# Main.net
KiCad netlist of a schematic drawn in Altium Designer
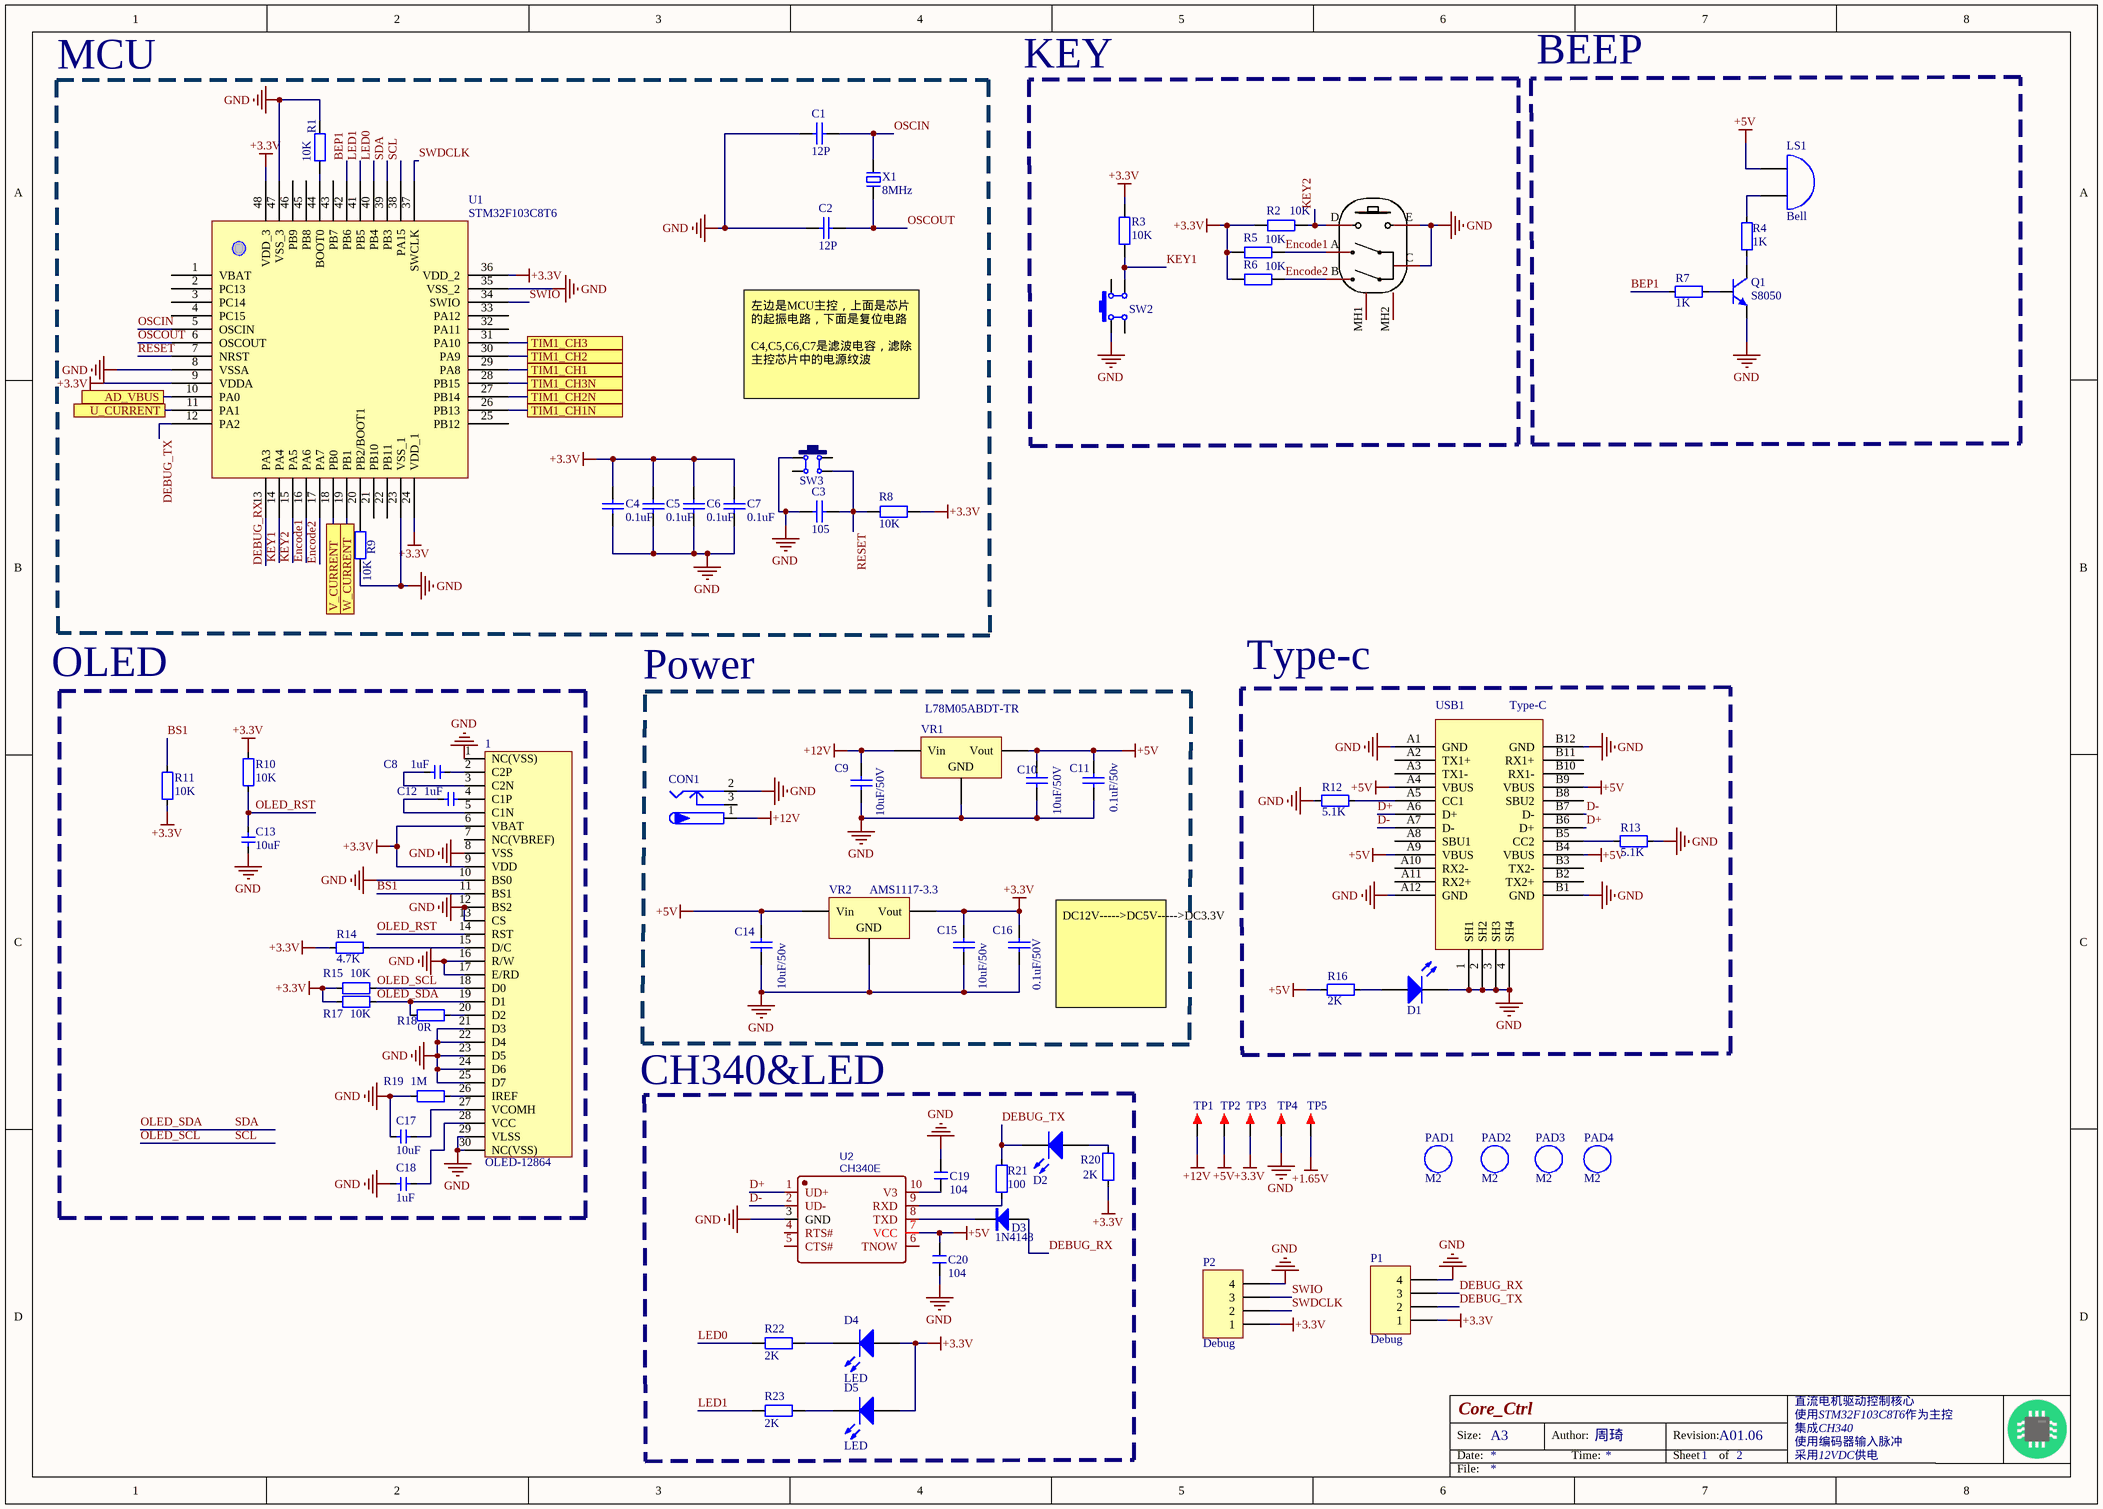
[diagram p0: Main.SchDoc]

(export (version "E")
  (design (tool "Eeschema 10.0.6"))
  (components
    (comp (ref "1")
      (value "OLED-12864")
      (footprint "OLED-12864-1.3-TOP")
      (description "显示屏")
      (libsource (lib "MyPcbLib") (part "OLED-12864"))
    )
    (comp (ref "C1")
      (value "12P")
      (footprint "C0603_L")
      (description "贴片电容")
      (libsource (lib "0.1 - 电阻-电容-电感-磁珠-电位器") (part "C"))
    )
    (comp (ref "C2")
      (value "12P")
      (footprint "C0603_L")
      (description "贴片电容")
      (libsource (lib "0.1 - 电阻-电容-电感-磁珠-电位器") (part "C"))
    )
    (comp (ref "C3")
      (value "105")
      (footprint "C0603_L")
      (description "贴片电容")
      (libsource (lib "0.1 - 电阻-电容-电感-磁珠-电位器") (part "C"))
    )
    (comp (ref "C4")
      (value "0.1uF")
      (footprint "C0603_L")
      (description "贴片电容")
      (libsource (lib "0.1 - 电阻-电容-电感-磁珠-电位器") (part "C"))
    )
    (comp (ref "C5")
      (value "0.1uF")
      (footprint "C0603_L")
      (description "贴片电容")
      (libsource (lib "0.1 - 电阻-电容-电感-磁珠-电位器") (part "C"))
    )
    (comp (ref "C6")
      (value "0.1uF")
      (footprint "C0603_L")
      (description "贴片电容")
      (libsource (lib "0.1 - 电阻-电容-电感-磁珠-电位器") (part "C"))
    )
    (comp (ref "C7")
      (value "0.1uF")
      (footprint "C0603_L")
      (description "贴片电容")
      (libsource (lib "0.1 - 电阻-电容-电感-磁珠-电位器") (part "C"))
    )
    (comp (ref "C8")
      (value "1uF")
      (footprint "C0603_L")
      (description "Capacitor")
      (libsource (lib "MyPcbLib") (part "电容-0402"))
    )
    (comp (ref "C9")
      (value "10uF/50V")
      (footprint "C1206_L")
      (description "C89632")
      (libsource (lib "Miscellaneous Devices") (part "Cap"))
    )
    (comp (ref "C10")
      (value "10uF/50V")
      (footprint "C1206_L")
      (description "C89632")
      (libsource (lib "Miscellaneous Devices") (part "Cap"))
    )
    (comp (ref "C11")
      (value "0.1uF/50v")
      (footprint "C1206_L")
      (libsource (lib "Miscellaneous Devices") (part "Cap"))
    )
    (comp (ref "C12")
      (value "1uF")
      (footprint "C0603_L")
      (description "Capacitor")
      (libsource (lib "MyPcbLib") (part "电容-0402"))
    )
    (comp (ref "C13")
      (value "10uF")
      (footprint "C0603_L")
      (description "Capacitor")
      (libsource (lib "MyPcbLib") (part "电容-0402"))
    )
    (comp (ref "C14")
      (value "10uF/50v")
      (footprint "C1206_L")
      (libsource (lib "Miscellaneous Devices") (part "Cap"))
    )
    (comp (ref "C15")
      (value "10uF/50v")
      (footprint "C1206_L")
      (libsource (lib "Miscellaneous Devices") (part "Cap"))
    )
    (comp (ref "C16")
      (value "0.1uF/50V")
      (footprint "C0603_L")
      (description "C89632")
      (libsource (lib "Miscellaneous Devices") (part "Cap"))
    )
    (comp (ref "C17")
      (value "10uF")
      (footprint "C0603_L")
      (description "Capacitor")
      (libsource (lib "MyPcbLib") (part "电容-0402"))
    )
    (comp (ref "C18")
      (value "1uF")
      (footprint "C0603_L")
      (description "Capacitor")
      (libsource (lib "MyPcbLib") (part "电容-0402"))
    )
    (comp (ref "C19")
      (value "104")
      (footprint "C0603_L")
      (description "无极性贴片电容")
      (fields (field (name "版权归属") "源创客"))
      (libsource (lib "9-电阻-电容-电感") (part "C"))
    )
    (comp (ref "C20")
      (value "104")
      (footprint "C0603_L")
      (description "无极性贴片电容")
      (fields (field (name "版权归属") "源创客"))
      (libsource (lib "9-电阻-电容-电感") (part "C"))
    )
    (comp (ref "CON1")
      (value "3.5*1.3")
      (footprint "DC-005")
      (description "低压电源接口")
      (libsource (lib "0.8 - 以太网-音频-Type-C USB插座") (part "P-DC"))
    )
    (comp (ref "D1")
      (value "LED0")
      (footprint "LED0603_R")
      (description "发光二极管")
      (fields (field (name "PUBLISHER") "Altium Limited"))
      (libsource (lib "18-常用器件") (part "LED0"))
    )
    (comp (ref "D2")
      (value "LED0")
      (footprint "LED0603_G")
      (description "发光二极管")
      (fields (field (name "PUBLISHER") "Altium Limited"))
      (libsource (lib "18-常用器件") (part "LED0"))
    )
    (comp (ref "D3")
      (value "1N4148")
      (footprint "SOD-123")
      (description "整流二极管")
      (fields (field (name "版权归属") "源创客"))
      (libsource (lib "10-二极管-整流桥") (part "M7"))
    )
    (comp (ref "D4")
      (value "LED")
      (footprint "LED0603_B")
      (description "发光二极管")
      (libsource (lib "0.3 - LED发光二极管") (part "LED"))
    )
    (comp (ref "D5")
      (value "LED")
      (footprint "LED0603_B")
      (description "发光二极管")
      (libsource (lib "0.3 - LED发光二极管") (part "LED"))
    )
    (comp (ref "LS1")
      (value "Bell")
      (footprint "BEEP 5x9x5.5")
      (description "Electrical Bell")
      (fields (field (name "PUBLISHER") "Altium Limited"))
      (libsource (lib "Miscellaneous Devices") (part "Bell"))
    )
    (comp (ref "P1")
      (value "Debug")
      (footprint "HDR2.54-LI-4P")
      (description "Header, 4-Pin")
      (fields (field (name "PUBLISHER") "Altium Limited"))
      (libsource (lib "Miscellaneous Connectors") (part "Header 4"))
    )
    (comp (ref "P2")
      (value "Debug")
      (footprint "HDR2.54-LI-4P")
      (description "Header, 4-Pin")
      (fields (field (name "PUBLISHER") "Altium Limited"))
      (libsource (lib "Miscellaneous Connectors") (part "Header 4"))
    )
    (comp (ref "PAD1")
      (value "M2")
      (footprint "M2")
      (description "铜柱孔")
      (libsource (lib "0.7 - 常用按键-开关-蜂鸣器-电池-测试点") (part "M3"))
    )
    (comp (ref "PAD2")
      (value "M2")
      (footprint "M2")
      (description "铜柱孔")
      (libsource (lib "0.7 - 常用按键-开关-蜂鸣器-电池-测试点") (part "M3"))
    )
    (comp (ref "PAD3")
      (value "M2")
      (footprint "M2")
      (description "铜柱孔")
      (libsource (lib "0.7 - 常用按键-开关-蜂鸣器-电池-测试点") (part "M3"))
    )
    (comp (ref "PAD4")
      (value "M2")
      (footprint "M2")
      (description "铜柱孔")
      (libsource (lib "0.7 - 常用按键-开关-蜂鸣器-电池-测试点") (part "M3"))
    )
    (comp (ref "Q1")
      (value "S8050")
      (footprint "SOT23-3N")
      (description "高频放大-NPN型")
      (libsource (lib "0.4 - 三极管-场效应管-可控硅") (part "8050-SMD"))
    )
    (comp (ref "R1")
      (value "10K")
      (footprint "R0603_L")
      (description "贴片电阻")
      (libsource (lib "0.1 - 电阻-电容-电感-磁珠-电位器") (part "R"))
    )
    (comp (ref "R2")
      (value "10K")
      (footprint "R0603_L")
      (description "贴片电阻")
      (libsource (lib "0.1 - 电阻-电容-电感-磁珠-电位器") (part "R"))
    )
    (comp (ref "R3")
      (value "10K")
      (footprint "R0603_L")
      (description "贴片电阻")
      (libsource (lib "0.1 - 电阻-电容-电感-磁珠-电位器") (part "R"))
    )
    (comp (ref "R4")
      (value "1K")
      (footprint "R0603_L")
      (description "Resistor")
      (libsource (lib "MyPcbLib") (part "电阻-0402"))
    )
    (comp (ref "R5")
      (value "10K")
      (footprint "R0603_L")
      (description "贴片电阻")
      (libsource (lib "0.1 - 电阻-电容-电感-磁珠-电位器") (part "R"))
    )
    (comp (ref "R6")
      (value "10K")
      (footprint "R0603_L")
      (description "贴片电阻")
      (libsource (lib "0.1 - 电阻-电容-电感-磁珠-电位器") (part "R"))
    )
    (comp (ref "R7")
      (value "1K")
      (footprint "R0603_L")
      (description "Resistor")
      (libsource (lib "") (part "电阻-0402_1"))
    )
    (comp (ref "R8")
      (value "10K")
      (footprint "R0603_L")
      (description "贴片电阻")
      (libsource (lib "0.1 - 电阻-电容-电感-磁珠-电位器") (part "R"))
    )
    (comp (ref "R9")
      (value "10K")
      (footprint "R0603_L")
      (description "贴片电阻")
      (libsource (lib "0.1 - 电阻-电容-电感-磁珠-电位器") (part "R"))
    )
    (comp (ref "R10")
      (value "10K")
      (footprint "R0603_L")
      (description "Resistor")
      (libsource (lib "MyPcbLib") (part "电阻-0402"))
    )
    (comp (ref "R11")
      (value "10K")
      (footprint "R0603_L")
      (description "Resistor")
      (libsource (lib "MyPcbLib") (part "电阻-0402"))
    )
    (comp (ref "R12")
      (value "5.1K")
      (footprint "R0603_L")
      (description "Resistor")
      (libsource (lib "") (part "电阻-0402_1"))
    )
    (comp (ref "R13")
      (value "5.1K")
      (footprint "R0603_L")
      (description "Resistor")
      (libsource (lib "") (part "电阻-0402_2"))
    )
    (comp (ref "R14")
      (value "4.7K")
      (footprint "R0603_L")
      (description "Resistor")
      (libsource (lib "") (part "电阻-0402_2"))
    )
    (comp (ref "R15")
      (value "10K")
      (footprint "R0603_L")
      (description "Resistor")
      (libsource (lib "") (part "电阻-0402_1"))
    )
    (comp (ref "R16")
      (value "2K")
      (footprint "R0603_L")
      (description "Resistor")
      (libsource (lib "") (part "电阻-0402_1"))
    )
    (comp (ref "R17")
      (value "10K")
      (footprint "R0603_L")
      (description "Resistor")
      (libsource (lib "") (part "电阻-0402_1"))
    )
    (comp (ref "R18")
      (value "0R")
      (footprint "R0603_L")
      (description "Resistor")
      (libsource (lib "") (part "电阻-0402_2"))
    )
    (comp (ref "R19")
      (value "1M")
      (footprint "R0603_L")
      (description "Resistor")
      (libsource (lib "") (part "电阻-0402_1"))
    )
    (comp (ref "R20")
      (value "2K")
      (footprint "R0603_L")
      (description "Resistor")
      (libsource (lib "MyPcbLib") (part "电阻-0402"))
    )
    (comp (ref "R21")
      (value "100")
      (footprint "R0603_L")
      (description "Resistor")
      (libsource (lib "") (part "电阻-0402_3"))
    )
    (comp (ref "R22")
      (value "2K")
      (footprint "R0603_L")
      (description "贴片电阻")
      (libsource (lib "0.1 - 电阻-电容-电感-磁珠-电位器") (part "R"))
    )
    (comp (ref "R23")
      (value "2K")
      (footprint "R0603_L")
      (description "贴片电阻")
      (libsource (lib "0.1 - 电阻-电容-电感-磁珠-电位器") (part "R"))
    )
    (comp (ref "SW1")
      (value "EC11K1524406")
      (footprint "SW-TH_EC11K1524406")
      (fields (field (name "MANUFACTURER") "ALPSALPINE(阿尔卑斯阿尔派)"))
      (libsource (lib "altium-import") (part "root_0_EC11K1524406_"))
    )
    (comp (ref "SW2")
      (value "12x12x5")
      (footprint "SW DIP-12*12*4.3")
      (description "直插12x12轻触开关")
      (libsource (lib "0.7 - 常用按键-开关-蜂鸣器-电池-测试点") (part "TSW DIP-12x12"))
    )
    (comp (ref "SW3")
      (value "6x6x5")
      (footprint "SW SMD-6*6*5")
      (description "贴片6x6轻触开关")
      (fields (field (name "版权归属") "源创客"))
      (libsource (lib "5-按键-开关") (part "TSW SMD-6x6"))
    )
    (comp (ref "TP1")
      (value "TEST")
      (footprint "TEST 1.6")
      (description "测试点")
      (libsource (lib "0.7 - 常用按键-开关-蜂鸣器-电池-测试点") (part "TEST"))
    )
    (comp (ref "TP2")
      (value "TEST")
      (footprint "TEST 1.6")
      (description "测试点")
      (libsource (lib "0.7 - 常用按键-开关-蜂鸣器-电池-测试点") (part "TEST"))
    )
    (comp (ref "TP3")
      (value "TEST")
      (footprint "TEST 1.6")
      (description "测试点")
      (libsource (lib "0.7 - 常用按键-开关-蜂鸣器-电池-测试点") (part "TEST"))
    )
    (comp (ref "TP4")
      (value "TEST")
      (footprint "TEST 1.6")
      (description "测试点")
      (libsource (lib "0.7 - 常用按键-开关-蜂鸣器-电池-测试点") (part "TEST"))
    )
    (comp (ref "TP5")
      (value "TEST")
      (footprint "TEST 1.6")
      (description "测试点")
      (libsource (lib "0.7 - 常用按键-开关-蜂鸣器-电池-测试点") (part "TEST"))
    )
    (comp (ref "U1")
      (value "STM32F103C8T6")
      (footprint "LQFP48-7*7")
      (libsource (lib "STM32F103C8T6") (part "STM32F103C8T6"))
    )
    (comp (ref "U2")
      (value "CH340E")
      (footprint "MSOP10_M")
      (fields (field (name "BOM_SUPPLIER PART") "C99652") (field (name "SUBPART_NO") "1"))
      (libsource (lib "altium-import") (part "root_0_CH340E_"))
    )
    (comp (ref "USB1")
      (value "Type-C")
      (footprint "USB-C-SMD_16P")
      (libsource (lib "MyPcbLib") (part "USB-Type-C-TOP"))
    )
    (comp (ref "VR1")
      (value "L78M05ABDT-TR")
      (footprint "TO-252")
      (description "低压差线性稳压(LDO)")
      (libsource (lib "LDO") (part "TO-252-2 L78M05ABDT-TR"))
    )
    (comp (ref "VR2")
      (value "AMS1117-3.3")
      (footprint "SOT223_L")
      (description "低压差线性稳压(LDO)")
      (libsource (lib "Miscellaneous Devices LC") (part "SOT-223 AMS1117-3.3"))
    )
    (comp (ref "X1")
      (value "8MHz")
      (footprint "OSC HC-49SMD")
      (description "2脚无源脚晶振")
      (libsource (lib "0.5 - 保险丝-晶振-光耦") (part "XTAL-2P"))
    )
  )
  (nets
    (net (code "1") (name "+1.65V") (class "Default")
      (node (ref "TP5") (pin "1") (pinfunction "1_1") (pintype "passive"))
    )
    (net (code "2") (name "+3.3V") (class "Default")
      (node (ref "1") (pin "6") (pinfunction "VBAT_6") (pintype "passive"))
      (node (ref "1") (pin "9") (pinfunction "VDD_9") (pintype "passive"))
      (node (ref "C15") (pin "2") (pinfunction "2_2") (pintype "passive"))
      (node (ref "C16") (pin "2") (pinfunction "2_2") (pintype "passive"))
      (node (ref "C4") (pin "1") (pinfunction "1_1") (pintype "passive"))
      (node (ref "C5") (pin "1") (pinfunction "1_1") (pintype "passive"))
      (node (ref "C6") (pin "1") (pinfunction "1_1") (pintype "passive"))
      (node (ref "C7") (pin "1") (pinfunction "1_1") (pintype "passive"))
      (node (ref "D4") (pin "1") (pinfunction "A_1") (pintype "passive"))
      (node (ref "D5") (pin "1") (pinfunction "A_1") (pintype "passive"))
      (node (ref "P1") (pin "1") (pinfunction "1_1") (pintype "passive"))
      (node (ref "P2") (pin "1") (pinfunction "1_1") (pintype "passive"))
      (node (ref "R10") (pin "2") (pinfunction "2_2") (pintype "passive"))
      (node (ref "R11") (pin "1") (pinfunction "1_1") (pintype "passive"))
      (node (ref "R14") (pin "2") (pinfunction "2_2") (pintype "passive"))
      (node (ref "R15") (pin "1") (pinfunction "1_1") (pintype "passive"))
      (node (ref "R17") (pin "1") (pinfunction "1_1") (pintype "passive"))
      (node (ref "R2") (pin "2") (pinfunction "2_2") (pintype "passive"))
      (node (ref "R20") (pin "1") (pinfunction "1_1") (pintype "passive"))
      (node (ref "R3") (pin "2") (pinfunction "2_2") (pintype "passive"))
      (node (ref "R5") (pin "2") (pinfunction "2_2") (pintype "passive"))
      (node (ref "R6") (pin "2") (pinfunction "2_2") (pintype "passive"))
      (node (ref "R8") (pin "2") (pinfunction "2_2") (pintype "passive"))
      (node (ref "TP3") (pin "1") (pinfunction "1_1") (pintype "passive"))
      (node (ref "U1") (pin "24") (pinfunction "VDD_1_24") (pintype "passive"))
      (node (ref "U1") (pin "36") (pinfunction "VDD_2_36") (pintype "passive"))
      (node (ref "U1") (pin "48") (pinfunction "VDD_3_48") (pintype "passive"))
      (node (ref "U1") (pin "9") (pinfunction "VDDA_9") (pintype "passive"))
      (node (ref "VR2") (pin "2") (pinfunction "Vout_2") (pintype "passive"))
    )
    (net (code "3") (name "+5V") (class "Default")
      (node (ref "C10") (pin "2") (pinfunction "2_2") (pintype "passive"))
      (node (ref "C11") (pin "2") (pinfunction "2_2") (pintype "passive"))
      (node (ref "C14") (pin "2") (pinfunction "2_2") (pintype "passive"))
      (node (ref "C20") (pin "1") (pinfunction "1_1") (pintype "passive"))
      (node (ref "LS1") (pin "1") (pinfunction "A_1") (pintype "passive"))
      (node (ref "R16") (pin "1") (pinfunction "1_1") (pintype "passive"))
      (node (ref "TP2") (pin "1") (pinfunction "1_1") (pintype "passive"))
      (node (ref "U2") (pin "7") (pinfunction "VCC_7") (pintype "passive"))
      (node (ref "USB1") (pin "A4") (pinfunction "VBUS_A4") (pintype "passive"))
      (node (ref "USB1") (pin "A9") (pinfunction "VBUS_A9") (pintype "passive"))
      (node (ref "USB1") (pin "B4") (pinfunction "VBUS_B4") (pintype "passive"))
      (node (ref "USB1") (pin "B9") (pinfunction "VBUS_B9") (pintype "passive"))
      (node (ref "VR1") (pin "3") (pinfunction "Vout_3") (pintype "passive"))
      (node (ref "VR2") (pin "3") (pinfunction "Vin_3") (pintype "passive"))
    )
    (net (code "4") (name "+12V") (class "Default")
      (node (ref "C9") (pin "2") (pinfunction "2_2") (pintype "passive"))
      (node (ref "CON1") (pin "1") (pintype "power_in"))
      (node (ref "TP1") (pin "1") (pinfunction "1_1") (pintype "passive"))
      (node (ref "VR1") (pin "1") (pinfunction "Vin_1") (pintype "passive"))
    )
    (net (code "5") (name "/AD_VBUS") (class "Default")
      (node (ref "U1") (pin "10") (pinfunction "PA0_10") (pintype "passive"))
    )
    (net (code "6") (name "/BEP1") (class "Default")
      (node (ref "R7") (pin "1") (pinfunction "1_1") (pintype "passive"))
      (node (ref "U1") (pin "42") (pinfunction "PB6_42") (pintype "passive"))
    )
    (net (code "7") (name "/BS1") (class "Default")
      (node (ref "1") (pin "11") (pinfunction "BS1_11") (pintype "passive"))
      (node (ref "R11") (pin "2") (pinfunction "2_2") (pintype "passive"))
    )
    (net (code "8") (name "/D+") (class "Default")
      (node (ref "U2") (pin "1") (pinfunction "UD+_1") (pintype "passive"))
      (node (ref "USB1") (pin "A6") (pinfunction "D+_A6") (pintype "passive"))
      (node (ref "USB1") (pin "B6") (pinfunction "D+_B6") (pintype "passive"))
    )
    (net (code "9") (name "/D-") (class "Default")
      (node (ref "U2") (pin "2") (pinfunction "UD-_2") (pintype "passive"))
      (node (ref "USB1") (pin "A7") (pinfunction "D-_A7") (pintype "passive"))
      (node (ref "USB1") (pin "B7") (pinfunction "D-_B7") (pintype "passive"))
    )
    (net (code "10") (name "/DEBUG_RX") (class "Default")
      (node (ref "D3") (pin "1") (pinfunction "A_1") (pintype "passive"))
      (node (ref "P1") (pin "3") (pinfunction "3_3") (pintype "passive"))
      (node (ref "U1") (pin "13") (pinfunction "PA3_13") (pintype "passive"))
    )
    (net (code "11") (name "/DEBUG_TX") (class "Default")
      (node (ref "D2") (pin "2") (pinfunction "K_2") (pintype "passive"))
      (node (ref "P1") (pin "2") (pinfunction "2_2") (pintype "passive"))
      (node (ref "R21") (pin "1") (pinfunction "1_1") (pintype "passive"))
      (node (ref "U1") (pin "12") (pinfunction "PA2_12") (pintype "passive"))
    )
    (net (code "12") (name "/Encode1") (class "Default")
      (node (ref "R5") (pin "1") (pinfunction "1_1") (pintype "passive"))
      (node (ref "SW1") (pin "A") (pinfunction "A_A") (pintype "passive"))
      (node (ref "U1") (pin "16") (pinfunction "PA6_16") (pintype "passive"))
    )
    (net (code "13") (name "/Encode2") (class "Default")
      (node (ref "R6") (pin "1") (pinfunction "1_1") (pintype "passive"))
      (node (ref "SW1") (pin "B") (pinfunction "B_B") (pintype "passive"))
      (node (ref "U1") (pin "17") (pinfunction "PA7_17") (pintype "passive"))
    )
    (net (code "14") (name "/KEY1") (class "Default")
      (node (ref "R3") (pin "1") (pinfunction "1_1") (pintype "passive"))
      (node (ref "SW2") (pin "3") (pinfunction "3_3") (pintype "passive"))
      (node (ref "U1") (pin "14") (pinfunction "PA4_14") (pintype "passive"))
    )
    (net (code "15") (name "/KEY2") (class "Default")
      (node (ref "R2") (pin "1") (pinfunction "1_1") (pintype "passive"))
      (node (ref "SW1") (pin "D") (pinfunction "D_D") (pintype "passive"))
      (node (ref "U1") (pin "15") (pinfunction "PA5_15") (pintype "passive"))
    )
    (net (code "16") (name "/LED0") (class "Default")
      (node (ref "R22") (pin "2") (pinfunction "2_2") (pintype "passive"))
      (node (ref "U1") (pin "40") (pinfunction "PB4_40") (pintype "passive"))
    )
    (net (code "17") (name "/LED1") (class "Default")
      (node (ref "R23") (pin "2") (pinfunction "2_2") (pintype "passive"))
      (node (ref "U1") (pin "41") (pinfunction "PB5_41") (pintype "passive"))
    )
    (net (code "18") (name "/OLED_RST") (class "Default")
      (node (ref "1") (pin "14") (pinfunction "RST_14") (pintype "passive"))
      (node (ref "C13") (pin "2") (pinfunction "2_2") (pintype "passive"))
      (node (ref "R10") (pin "1") (pinfunction "1_1") (pintype "passive"))
    )
    (net (code "19") (name "/OLED_SCL") (class "Default")
      (node (ref "1") (pin "18") (pinfunction "D0_18") (pintype "passive"))
      (node (ref "R15") (pin "2") (pinfunction "2_2") (pintype "passive"))
      (node (ref "U1") (pin "38") (pinfunction "PA15_38") (pintype "passive"))
    )
    (net (code "20") (name "/OLED_SDA") (class "Default")
      (node (ref "1") (pin "19") (pinfunction "D1_19") (pintype "passive"))
      (node (ref "R17") (pin "2") (pinfunction "2_2") (pintype "passive"))
      (node (ref "R18") (pin "2") (pinfunction "2_2") (pintype "passive"))
      (node (ref "U1") (pin "39") (pinfunction "PB3_39") (pintype "passive"))
    )
    (net (code "21") (name "/OSCIN") (class "Default")
      (node (ref "C1") (pin "2") (pinfunction "2_2") (pintype "passive"))
      (node (ref "U1") (pin "5") (pinfunction "OSCIN_5") (pintype "passive"))
      (node (ref "X1") (pin "2") (pinfunction "2_2") (pintype "passive"))
    )
    (net (code "22") (name "/OSCOUT") (class "Default")
      (node (ref "C2") (pin "2") (pinfunction "2_2") (pintype "passive"))
      (node (ref "U1") (pin "6") (pinfunction "OSCOUT_6") (pintype "passive"))
      (node (ref "X1") (pin "1") (pinfunction "1_1") (pintype "passive"))
    )
    (net (code "23") (name "/RESET") (class "Default")
      (node (ref "C3") (pin "2") (pinfunction "2_2") (pintype "passive"))
      (node (ref "R8") (pin "1") (pinfunction "1_1") (pintype "passive"))
      (node (ref "SW3") (pin "3") (pinfunction "3_3") (pintype "passive"))
      (node (ref "U1") (pin "7") (pinfunction "NRST_7") (pintype "passive"))
    )
    (net (code "24") (name "/SWDCLK") (class "Default")
      (node (ref "P2") (pin "2") (pinfunction "2_2") (pintype "passive"))
      (node (ref "U1") (pin "37") (pinfunction "SWCLK_37") (pintype "passive"))
    )
    (net (code "25") (name "/SWIO") (class "Default")
      (node (ref "P2") (pin "3") (pinfunction "3_3") (pintype "passive"))
      (node (ref "U1") (pin "34") (pinfunction "SWIO_34") (pintype "passive"))
    )
    (net (code "26") (name "/TIM1_CH1") (class "Default")
      (node (ref "U1") (pin "29") (pinfunction "PA8_29") (pintype "passive"))
    )
    (net (code "27") (name "/TIM1_CH1N") (class "Default")
      (node (ref "U1") (pin "26") (pinfunction "PB13_26") (pintype "passive"))
    )
    (net (code "28") (name "/TIM1_CH2") (class "Default")
      (node (ref "U1") (pin "30") (pinfunction "PA9_30") (pintype "passive"))
    )
    (net (code "29") (name "/TIM1_CH2N") (class "Default")
      (node (ref "U1") (pin "27") (pinfunction "PB14_27") (pintype "passive"))
    )
    (net (code "30") (name "/TIM1_CH3") (class "Default")
      (node (ref "U1") (pin "31") (pinfunction "PA10_31") (pintype "passive"))
    )
    (net (code "31") (name "/TIM1_CH3N") (class "Default")
      (node (ref "U1") (pin "28") (pinfunction "PB15_28") (pintype "passive"))
    )
    (net (code "32") (name "/U_CURRENT") (class "Default")
      (node (ref "U1") (pin "11") (pinfunction "PA1_11") (pintype "passive"))
    )
    (net (code "33") (name "/V_CURRENT") (class "Default")
      (node (ref "U1") (pin "18") (pinfunction "PB0_18") (pintype "passive"))
    )
    (net (code "34") (name "/W_CURRENT") (class "Default")
      (node (ref "U1") (pin "19") (pinfunction "PB1_19") (pintype "passive"))
    )
    (net (code "35") (name "GND") (class "Default")
      (node (ref "1") (pin "1") (pinfunction "NC(VSS)_1") (pintype "passive"))
      (node (ref "1") (pin "10") (pinfunction "BS0_10") (pintype "passive"))
      (node (ref "1") (pin "12") (pinfunction "BS2_12") (pintype "passive"))
      (node (ref "1") (pin "13") (pinfunction "CS_13") (pintype "passive"))
      (node (ref "1") (pin "16") (pinfunction "R/W_16") (pintype "passive"))
      (node (ref "1") (pin "17") (pinfunction "E/RD_17") (pintype "passive"))
      (node (ref "1") (pin "21") (pinfunction "D3_21") (pintype "passive"))
      (node (ref "1") (pin "22") (pinfunction "D4_22") (pintype "passive"))
      (node (ref "1") (pin "23") (pinfunction "D5_23") (pintype "passive"))
      (node (ref "1") (pin "24") (pinfunction "D6_24") (pintype "passive"))
      (node (ref "1") (pin "25") (pinfunction "D7_25") (pintype "passive"))
      (node (ref "1") (pin "29") (pinfunction "VLSS_29") (pintype "passive"))
      (node (ref "1") (pin "30") (pinfunction "NC(VSS)_30") (pintype "passive"))
      (node (ref "1") (pin "8") (pinfunction "VSS_8") (pintype "passive"))
      (node (ref "C1") (pin "1") (pinfunction "1_1") (pintype "passive"))
      (node (ref "C10") (pin "1") (pinfunction "1_1") (pintype "passive"))
      (node (ref "C11") (pin "1") (pinfunction "1_1") (pintype "passive"))
      (node (ref "C13") (pin "1") (pinfunction "1_1") (pintype "passive"))
      (node (ref "C14") (pin "1") (pinfunction "1_1") (pintype "passive"))
      (node (ref "C15") (pin "1") (pinfunction "1_1") (pintype "passive"))
      (node (ref "C16") (pin "1") (pinfunction "1_1") (pintype "passive"))
      (node (ref "C17") (pin "2") (pinfunction "2_2") (pintype "passive"))
      (node (ref "C18") (pin "2") (pinfunction "2_2") (pintype "passive"))
      (node (ref "C19") (pin "1") (pinfunction "1_1") (pintype "passive"))
      (node (ref "C2") (pin "1") (pinfunction "1_1") (pintype "passive"))
      (node (ref "C20") (pin "2") (pinfunction "2_2") (pintype "passive"))
      (node (ref "C3") (pin "1") (pinfunction "1_1") (pintype "passive"))
      (node (ref "C4") (pin "2") (pinfunction "2_2") (pintype "passive"))
      (node (ref "C5") (pin "2") (pinfunction "2_2") (pintype "passive"))
      (node (ref "C6") (pin "2") (pinfunction "2_2") (pintype "passive"))
      (node (ref "C7") (pin "2") (pinfunction "2_2") (pintype "passive"))
      (node (ref "C9") (pin "1") (pinfunction "1_1") (pintype "passive"))
      (node (ref "CON1") (pin "2") (pintype "power_in"))
      (node (ref "D1") (pin "2") (pinfunction "K_2") (pintype "passive"))
      (node (ref "P1") (pin "4") (pinfunction "4_4") (pintype "passive"))
      (node (ref "P2") (pin "4") (pinfunction "4_4") (pintype "passive"))
      (node (ref "Q1") (pin "2") (pinfunction "E_2") (pintype "passive"))
      (node (ref "R1") (pin "2") (pinfunction "2_2") (pintype "passive"))
      (node (ref "R12") (pin "1") (pinfunction "1_1") (pintype "passive"))
      (node (ref "R13") (pin "1") (pinfunction "1_1") (pintype "passive"))
      (node (ref "R19") (pin "1") (pinfunction "1_1") (pintype "passive"))
      (node (ref "R9") (pin "1") (pinfunction "1_1") (pintype "passive"))
      (node (ref "SW1") (pin "C") (pinfunction "C_C") (pintype "passive"))
      (node (ref "SW1") (pin "E") (pinfunction "E_E") (pintype "passive"))
      (node (ref "SW2") (pin "1") (pinfunction "1_1") (pintype "passive"))
      (node (ref "SW3") (pin "1") (pinfunction "1_1") (pintype "passive"))
      (node (ref "TP4") (pin "1") (pinfunction "1_1") (pintype "passive"))
      (node (ref "U1") (pin "23") (pinfunction "VSS_1_23") (pintype "passive"))
      (node (ref "U1") (pin "35") (pinfunction "VSS_2_35") (pintype "passive"))
      (node (ref "U1") (pin "47") (pinfunction "VSS_3_47") (pintype "passive"))
      (node (ref "U1") (pin "8") (pinfunction "VSSA_8") (pintype "passive"))
      (node (ref "U2") (pin "3") (pinfunction "GND_3") (pintype "passive"))
      (node (ref "USB1") (pin "1") (pinfunction "SH1_1") (pintype "passive"))
      (node (ref "USB1") (pin "2") (pinfunction "SH2_2") (pintype "passive"))
      (node (ref "USB1") (pin "3") (pinfunction "SH3_3") (pintype "passive"))
      (node (ref "USB1") (pin "4") (pinfunction "SH4_4") (pintype "passive"))
      (node (ref "USB1") (pin "A1") (pinfunction "GND_A1") (pintype "passive"))
      (node (ref "USB1") (pin "A12") (pinfunction "GND_A12") (pintype "passive"))
      (node (ref "USB1") (pin "B1") (pinfunction "GND_B1") (pintype "passive"))
      (node (ref "USB1") (pin "B12") (pinfunction "GND_B12") (pintype "passive"))
      (node (ref "VR1") (pin "2") (pinfunction "GND_2") (pintype "passive"))
      (node (ref "VR2") (pin "1") (pinfunction "GND_1") (pintype "passive"))
    )
    (net (code "36") (name "Net-(1-C1N)") (class "Default")
      (node (ref "1") (pin "5") (pinfunction "C1N_5") (pintype "passive"))
      (node (ref "C12") (pin "2") (pinfunction "2_2") (pintype "passive"))
    )
    (net (code "37") (name "Net-(1-C1P)") (class "Default")
      (node (ref "1") (pin "4") (pinfunction "C1P_4") (pintype "passive"))
      (node (ref "C12") (pin "1") (pinfunction "1_1") (pintype "passive"))
    )
    (net (code "38") (name "Net-(1-C2N)") (class "Default")
      (node (ref "1") (pin "3") (pinfunction "C2N_3") (pintype "passive"))
      (node (ref "C8") (pin "2") (pinfunction "2_2") (pintype "passive"))
    )
    (net (code "39") (name "Net-(1-C2P)") (class "Default")
      (node (ref "1") (pin "2") (pinfunction "C2P_2") (pintype "passive"))
      (node (ref "C8") (pin "1") (pinfunction "1_1") (pintype "passive"))
    )
    (net (code "40") (name "Net-(1-D2)") (class "Default")
      (node (ref "1") (pin "20") (pinfunction "D2_20") (pintype "passive"))
      (node (ref "R18") (pin "1") (pinfunction "1_1") (pintype "passive"))
    )
    (net (code "41") (name "Net-(1-D{slash}C)") (class "Default")
      (node (ref "1") (pin "15") (pinfunction "D/C_15") (pintype "passive"))
      (node (ref "R14") (pin "1") (pinfunction "1_1") (pintype "passive"))
    )
    (net (code "42") (name "Net-(1-IREF)") (class "Default")
      (node (ref "1") (pin "26") (pinfunction "IREF_26") (pintype "passive"))
      (node (ref "R19") (pin "2") (pinfunction "2_2") (pintype "passive"))
    )
    (net (code "43") (name "Net-(1-VCC)") (class "Default")
      (node (ref "1") (pin "28") (pinfunction "VCC_28") (pintype "passive"))
      (node (ref "C18") (pin "1") (pinfunction "1_1") (pintype "passive"))
    )
    (net (code "44") (name "Net-(1-VCOMH)") (class "Default")
      (node (ref "1") (pin "27") (pinfunction "VCOMH_27") (pintype "passive"))
      (node (ref "C17") (pin "1") (pinfunction "1_1") (pintype "passive"))
    )
    (net (code "45") (name "Net-(D1-A)") (class "Default")
      (node (ref "D1") (pin "1") (pinfunction "A_1") (pintype "passive"))
      (node (ref "R16") (pin "2") (pinfunction "2_2") (pintype "passive"))
    )
    (net (code "46") (name "Net-(D2-A)") (class "Default")
      (node (ref "D2") (pin "1") (pinfunction "A_1") (pintype "passive"))
      (node (ref "R20") (pin "2") (pinfunction "2_2") (pintype "passive"))
    )
    (net (code "47") (name "Net-(D3-K)") (class "Default")
      (node (ref "D3") (pin "2") (pinfunction "K_2") (pintype "passive"))
      (node (ref "U2") (pin "8") (pinfunction "TXD_8") (pintype "passive"))
    )
    (net (code "48") (name "Net-(D4-K)") (class "Default")
      (node (ref "D4") (pin "2") (pinfunction "K_2") (pintype "passive"))
      (node (ref "R22") (pin "1") (pinfunction "1_1") (pintype "passive"))
    )
    (net (code "49") (name "Net-(D5-K)") (class "Default")
      (node (ref "D5") (pin "2") (pinfunction "K_2") (pintype "passive"))
      (node (ref "R23") (pin "1") (pinfunction "1_1") (pintype "passive"))
    )
    (net (code "50") (name "Net-(LS1-B)") (class "Default")
      (node (ref "LS1") (pin "2") (pinfunction "B_2") (pintype "passive"))
      (node (ref "R4") (pin "2") (pinfunction "2_2") (pintype "passive"))
    )
    (net (code "51") (name "Net-(Q1-B)") (class "Default")
      (node (ref "Q1") (pin "1") (pinfunction "B_1") (pintype "passive"))
      (node (ref "R7") (pin "2") (pinfunction "2_2") (pintype "passive"))
    )
    (net (code "52") (name "Net-(Q1-C)") (class "Default")
      (node (ref "Q1") (pin "3") (pinfunction "C_3") (pintype "passive"))
      (node (ref "R4") (pin "1") (pinfunction "1_1") (pintype "passive"))
    )
    (net (code "53") (name "Net-(U1-BOOT0)") (class "Default")
      (node (ref "R1") (pin "1") (pinfunction "1_1") (pintype "passive"))
      (node (ref "U1") (pin "44") (pinfunction "BOOT0_44") (pintype "passive"))
    )
    (net (code "54") (name "Net-(U1-PB2{slash}BOOT1)") (class "Default")
      (node (ref "R9") (pin "2") (pinfunction "2_2") (pintype "passive"))
      (node (ref "U1") (pin "20") (pinfunction "PB2/BOOT1_20") (pintype "passive"))
    )
    (net (code "55") (name "Net-(U2-RXD)") (class "Default")
      (node (ref "R21") (pin "2") (pinfunction "2_2") (pintype "passive"))
      (node (ref "U2") (pin "9") (pinfunction "RXD_9") (pintype "passive"))
    )
    (net (code "56") (name "Net-(U2-V3)") (class "Default")
      (node (ref "C19") (pin "2") (pinfunction "2_2") (pintype "passive"))
      (node (ref "U2") (pin "10") (pinfunction "V3_10") (pintype "passive"))
    )
    (net (code "57") (name "Net-(USB1-CC1)") (class "Default")
      (node (ref "R12") (pin "2") (pinfunction "2_2") (pintype "passive"))
      (node (ref "USB1") (pin "A5") (pinfunction "CC1_A5") (pintype "passive"))
    )
    (net (code "58") (name "Net-(USB1-CC2)") (class "Default")
      (node (ref "R13") (pin "2") (pinfunction "2_2") (pintype "passive"))
      (node (ref "USB1") (pin "B5") (pinfunction "CC2_B5") (pintype "passive"))
    )
    (net (code "59") (name "unconnected-(1-NC(VBREF)-Pad7)") (class "Default")
      (node (ref "1") (pin "7") (pinfunction "NC(VBREF)_7") (pintype "passive"))
    )
    (net (code "60") (name "unconnected-(CON1-Pad3)") (class "Default")
      (node (ref "CON1") (pin "3") (pintype "power_in"))
    )
    (net (code "61") (name "unconnected-(SW1-PadMH1)") (class "Default")
      (node (ref "SW1") (pin "MH1") (pinfunction "MH1_MH1") (pintype "passive"))
    )
    (net (code "62") (name "unconnected-(SW1-PadMH2)") (class "Default")
      (node (ref "SW1") (pin "MH2") (pinfunction "MH2_MH2") (pintype "passive"))
    )
    (net (code "63") (name "unconnected-(SW2-Pad2)") (class "Default")
      (node (ref "SW2") (pin "2") (pinfunction "2_2") (pintype "passive"))
    )
    (net (code "64") (name "unconnected-(SW2-Pad4)") (class "Default")
      (node (ref "SW2") (pin "4") (pinfunction "4_4") (pintype "passive"))
    )
    (net (code "65") (name "unconnected-(SW3-Pad2)") (class "Default")
      (node (ref "SW3") (pin "2") (pinfunction "2_2") (pintype "passive"))
    )
    (net (code "66") (name "unconnected-(SW3-Pad4)") (class "Default")
      (node (ref "SW3") (pin "4") (pinfunction "4_4") (pintype "passive"))
    )
    (net (code "67") (name "unconnected-(U1-PA11-Pad32)") (class "Default")
      (node (ref "U1") (pin "32") (pinfunction "PA11_32") (pintype "passive"))
    )
    (net (code "68") (name "unconnected-(U1-PA12-Pad33)") (class "Default")
      (node (ref "U1") (pin "33") (pinfunction "PA12_33") (pintype "passive"))
    )
    (net (code "69") (name "unconnected-(U1-PB7-Pad43)") (class "Default")
      (node (ref "U1") (pin "43") (pinfunction "PB7_43") (pintype "passive"))
    )
    (net (code "70") (name "unconnected-(U1-PB8-Pad45)") (class "Default")
      (node (ref "U1") (pin "45") (pinfunction "PB8_45") (pintype "passive"))
    )
    (net (code "71") (name "unconnected-(U1-PB9-Pad46)") (class "Default")
      (node (ref "U1") (pin "46") (pinfunction "PB9_46") (pintype "passive"))
    )
    (net (code "72") (name "unconnected-(U1-PB10-Pad21)") (class "Default")
      (node (ref "U1") (pin "21") (pinfunction "PB10_21") (pintype "passive"))
    )
    (net (code "73") (name "unconnected-(U1-PB11-Pad22)") (class "Default")
      (node (ref "U1") (pin "22") (pinfunction "PB11_22") (pintype "passive"))
    )
    (net (code "74") (name "unconnected-(U1-PB12-Pad25)") (class "Default")
      (node (ref "U1") (pin "25") (pinfunction "PB12_25") (pintype "passive"))
    )
    (net (code "75") (name "unconnected-(U1-PC13-Pad2)") (class "Default")
      (node (ref "U1") (pin "2") (pinfunction "PC13_2") (pintype "passive"))
    )
    (net (code "76") (name "unconnected-(U1-PC14-Pad3)") (class "Default")
      (node (ref "U1") (pin "3") (pinfunction "PC14_3") (pintype "passive"))
    )
    (net (code "77") (name "unconnected-(U1-PC15-Pad4)") (class "Default")
      (node (ref "U1") (pin "4") (pinfunction "PC15_4") (pintype "passive"))
    )
    (net (code "78") (name "unconnected-(U1-VBAT-Pad1)") (class "Default")
      (node (ref "U1") (pin "1") (pinfunction "VBAT_1") (pintype "passive"))
    )
    (net (code "79") (name "unconnected-(U2-CTS#-Pad5)") (class "Default")
      (node (ref "U2") (pin "5") (pinfunction "CTS#_5") (pintype "passive"))
    )
    (net (code "80") (name "unconnected-(U2-RTS#-Pad4)") (class "Default")
      (node (ref "U2") (pin "4") (pinfunction "RTS#_4") (pintype "passive"))
    )
    (net (code "81") (name "unconnected-(U2-TNOW-Pad6)") (class "Default")
      (node (ref "U2") (pin "6") (pinfunction "TNOW_6") (pintype "passive"))
    )
    (net (code "82") (name "unconnected-(USB1-RX1+-PadB11)") (class "Default")
      (node (ref "USB1") (pin "B11") (pinfunction "RX1+_B11") (pintype "passive"))
    )
    (net (code "83") (name "unconnected-(USB1-RX1--PadB10)") (class "Default")
      (node (ref "USB1") (pin "B10") (pinfunction "RX1-_B10") (pintype "passive"))
    )
    (net (code "84") (name "unconnected-(USB1-RX2+-PadA11)") (class "Default")
      (node (ref "USB1") (pin "A11") (pinfunction "RX2+_A11") (pintype "passive"))
    )
    (net (code "85") (name "unconnected-(USB1-RX2--PadA10)") (class "Default")
      (node (ref "USB1") (pin "A10") (pinfunction "RX2-_A10") (pintype "passive"))
    )
    (net (code "86") (name "unconnected-(USB1-SBU1-PadA8)") (class "Default")
      (node (ref "USB1") (pin "A8") (pinfunction "SBU1_A8") (pintype "passive"))
    )
    (net (code "87") (name "unconnected-(USB1-SBU2-PadB8)") (class "Default")
      (node (ref "USB1") (pin "B8") (pinfunction "SBU2_B8") (pintype "passive"))
    )
    (net (code "88") (name "unconnected-(USB1-TX1+-PadA2)") (class "Default")
      (node (ref "USB1") (pin "A2") (pinfunction "TX1+_A2") (pintype "passive"))
    )
    (net (code "89") (name "unconnected-(USB1-TX1--PadA3)") (class "Default")
      (node (ref "USB1") (pin "A3") (pinfunction "TX1-_A3") (pintype "passive"))
    )
    (net (code "90") (name "unconnected-(USB1-TX2+-PadB2)") (class "Default")
      (node (ref "USB1") (pin "B2") (pinfunction "TX2+_B2") (pintype "passive"))
    )
    (net (code "91") (name "unconnected-(USB1-TX2--PadB3)") (class "Default")
      (node (ref "USB1") (pin "B3") (pinfunction "TX2-_B3") (pintype "passive"))
    )
  )
)
